# mpu9250.net
KiCad netlist of a schematic drawn in Altium Designer
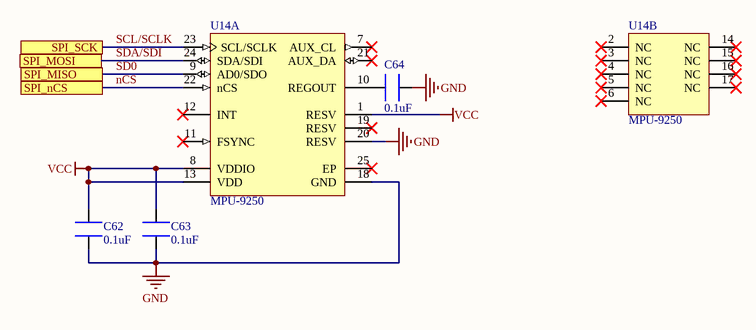
[diagram p0: mpu9250.SchDoc]

(export (version "E")
  (design (tool "Eeschema 10.0.6"))
  (components
    (comp (ref "C62")
      (value "0.1uF")
      (footprint "CAP 0603/1608")
      (description "CAP CER 0.1UF 25V X7R 0603")
      (fields (field (name "PARTNUMBER") "GRM188R71E104KA01D"))
      (libsource (lib "CustomComponents") (part "GRM188R71E104KA01D"))
    )
    (comp (ref "C63")
      (value "0.1uF")
      (footprint "CAP 0603/1608")
      (description "CAP CER 0.1UF 25V X7R 0603")
      (fields (field (name "PARTNUMBER") "GRM188R71E104KA01D"))
      (libsource (lib "CustomComponents") (part "GRM188R71E104KA01D"))
    )
    (comp (ref "C64")
      (value "0.1uF")
      (footprint "CAP 0603/1608")
      (description "CAP CER 0.1UF 25V X7R 0603")
      (fields (field (name "PARTNUMBER") "GRM188R71E104KA01D"))
      (libsource (lib "CustomComponents") (part "GRM188R71E104KA01D"))
    )
    (comp (ref "U14")
      (value "MPU-9250")
      (footprint "INSE-QFN-24-1700X1540TP_L")
      (description "9-axis MotionTracking device, 2.4 to 3,6 V, -40 to 85 degC, 24-Pin QFN, RoHS, Tape and Reel")
      (fields (field (name "MANUFACTURER") "InvenSense"))
      (libsource (lib "VESCuino_Extension_VER0.2_Lib") (part "CMP-2100-03657-1"))
    )
  )
  (nets
    (net (code "1") (name "/SCL{slash}SCLK") (class "Default")
      (node (ref "U14") (pin "23") (pinfunction "SCL/SCLK_23") (pintype "input"))
    )
    (net (code "2") (name "/SD0") (class "Default")
      (node (ref "U14") (pin "9") (pinfunction "AD0/SDO_9") (pintype "bidirectional"))
    )
    (net (code "3") (name "/SDA{slash}SDI") (class "Default")
      (node (ref "U14") (pin "24") (pinfunction "SDA/SDI_24") (pintype "bidirectional"))
    )
    (net (code "4") (name "/nCS") (class "Default")
      (node (ref "U14") (pin "22") (pinfunction "nCS_22") (pintype "input"))
    )
    (net (code "5") (name "GND") (class "Default")
      (node (ref "C62") (pin "2") (pinfunction "2_2") (pintype "passive"))
      (node (ref "C63") (pin "2") (pinfunction "2_2") (pintype "passive"))
      (node (ref "C64") (pin "1") (pinfunction "1_1") (pintype "passive"))
      (node (ref "U14") (pin "18") (pinfunction "GND_18") (pintype "power_in"))
      (node (ref "U14") (pin "20") (pinfunction "RESV_20") (pintype "power_in"))
    )
    (net (code "6") (name "Net-(U14A-REGOUT)") (class "Default")
      (node (ref "C64") (pin "2") (pinfunction "2_2") (pintype "passive"))
      (node (ref "U14") (pin "10") (pinfunction "REGOUT_10") (pintype "passive"))
    )
    (net (code "7") (name "VCC") (class "Default")
      (node (ref "C62") (pin "1") (pinfunction "1_1") (pintype "passive"))
      (node (ref "C63") (pin "1") (pinfunction "1_1") (pintype "passive"))
      (node (ref "U14") (pin "1") (pinfunction "RESV_1") (pintype "power_in"))
      (node (ref "U14") (pin "13") (pinfunction "VDD_13") (pintype "power_in"))
      (node (ref "U14") (pin "8") (pinfunction "VDDIO_8") (pintype "power_in"))
    )
    (net (code "8") (name "unconnected-(U14A-AUX_CL-Pad7)") (class "Default")
      (node (ref "U14") (pin "7") (pinfunction "AUX_CL_7") (pintype "output+no_connect"))
    )
    (net (code "9") (name "unconnected-(U14A-AUX_DA-Pad21)") (class "Default")
      (node (ref "U14") (pin "21") (pinfunction "AUX_DA_21") (pintype "bidirectional+no_connect"))
    )
    (net (code "10") (name "unconnected-(U14A-EP-Pad25)") (class "Default")
      (node (ref "U14") (pin "25") (pinfunction "EP_25") (pintype "passive+no_connect"))
    )
    (net (code "11") (name "unconnected-(U14A-FSYNC-Pad11)") (class "Default")
      (node (ref "U14") (pin "11") (pinfunction "FSYNC_11") (pintype "input+no_connect"))
    )
    (net (code "12") (name "unconnected-(U14A-INT-Pad12)") (class "Default")
      (node (ref "U14") (pin "12") (pinfunction "INT_12") (pintype "tri_state+no_connect"))
    )
    (net (code "13") (name "unconnected-(U14A-RESV-Pad19)") (class "Default")
      (node (ref "U14") (pin "19") (pinfunction "RESV_19") (pintype "passive+no_connect"))
    )
    (net (code "14") (name "unconnected-(U14B-NC-Pad2)") (class "Default")
      (node (ref "U14") (pin "2") (pinfunction "NC_2") (pintype "passive+no_connect"))
    )
    (net (code "15") (name "unconnected-(U14B-NC-Pad3)") (class "Default")
      (node (ref "U14") (pin "3") (pinfunction "NC_3") (pintype "passive+no_connect"))
    )
    (net (code "16") (name "unconnected-(U14B-NC-Pad4)") (class "Default")
      (node (ref "U14") (pin "4") (pinfunction "NC_4") (pintype "passive+no_connect"))
    )
    (net (code "17") (name "unconnected-(U14B-NC-Pad5)") (class "Default")
      (node (ref "U14") (pin "5") (pinfunction "NC_5") (pintype "passive+no_connect"))
    )
    (net (code "18") (name "unconnected-(U14B-NC-Pad6)") (class "Default")
      (node (ref "U14") (pin "6") (pinfunction "NC_6") (pintype "passive+no_connect"))
    )
    (net (code "19") (name "unconnected-(U14B-NC-Pad14)") (class "Default")
      (node (ref "U14") (pin "14") (pinfunction "NC_14") (pintype "passive+no_connect"))
    )
    (net (code "20") (name "unconnected-(U14B-NC-Pad15)") (class "Default")
      (node (ref "U14") (pin "15") (pinfunction "NC_15") (pintype "passive+no_connect"))
    )
    (net (code "21") (name "unconnected-(U14B-NC-Pad16)") (class "Default")
      (node (ref "U14") (pin "16") (pinfunction "NC_16") (pintype "passive+no_connect"))
    )
    (net (code "22") (name "unconnected-(U14B-NC-Pad17)") (class "Default")
      (node (ref "U14") (pin "17") (pinfunction "NC_17") (pintype "passive+no_connect"))
    )
  )
)
